# Schematic.net
KiCad netlist of a schematic drawn in Altium Designer
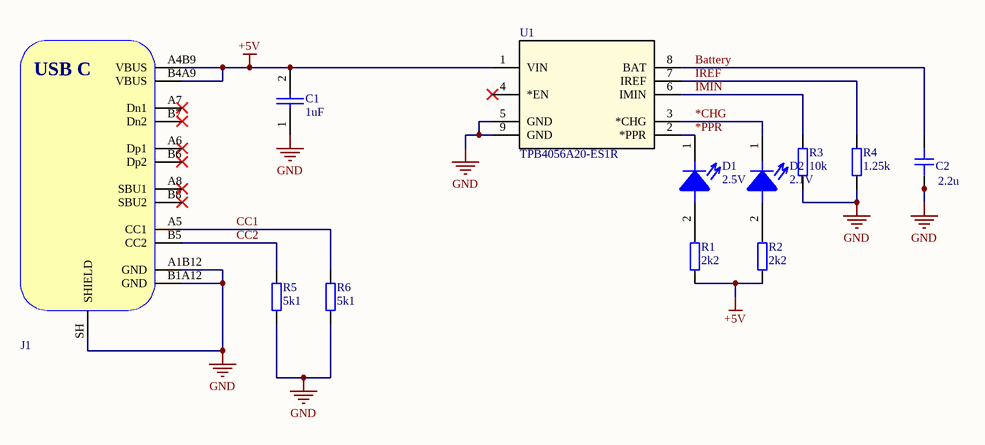
[diagram p0: Schematic.SchDoc]

(export (version "E")
  (design (tool "Eeschema 10.0.6"))
  (components
    (comp (ref "C1")
      (value "1uF")
      (footprint "CAP_0805")
      (description "CAP CER 1uF %10 0805")
      (fields
        (field (name "MANUFACTURER") "Samsung")
        (field (name "MANUFACTURER PART NUMBER") "CL21B105KBFNNNE")
        (field (name "DESIGNED BY") "Osman")
      )
      (libsource (lib "Integrated_Library1") (part "CAP CER 1uF 0805"))
    )
    (comp (ref "C2")
      (value "2.2u")
      (footprint "CAP 0805")
      (libsource (lib "Integrated_Library1") (part "CAP CER 2.2uF 16V 0805"))
    )
    (comp (ref "D1")
      (value "LS R976-NR-1")
      (footprint "LED_RED_0805")
      (description "LED Uni-Color Super Red 645nm 2-Pin Chip 0805(2012Metric) T/R")
      (fields
        (field (name "MANUFACTURER") "Osram Opto")
        (field (name "MANUFACTURER PART NUMBER") "LSR976-NR-1")
        (field (name "FORWARD VOLTAGE") "2.5V")
        (field (name "DESIGNED BY") "Osman")
      )
      (libsource (lib "Integrated_Library1") (part "LED RED 0805"))
    )
    (comp (ref "D2")
      (value "CMD17-21VGD/TR8")
      (footprint "LED_GREEN_0805")
      (description "CML CMD17-21VGD/TR8 LED SMT 0805 2.1V 7mcd 140deg Green 3K Part of the VCC Family of Products")
      (fields (field (name "MANUFACTURER") "VCC CHML") (field (name "FOWARD VOLTAGE") "2.1V"))
      (libsource (lib "Integrated_Library1") (part "LED GREEN 0805"))
    )
    (comp (ref "J1")
      (value "USB4105-GF-A-060")
      (footprint "USB4105-GF-A-060")
      (description "USB Connector, 24 Contact(s), Female, Right Angle, Solder Terminal, Locking, Receptacle")
      (fields (field (name "MANUFACTURER") "Global Connector Technology"))
      (libsource (lib "Integrated_Library1") (part "USB4105-GF-A-060"))
    )
    (comp (ref "R1")
      (value "2k2")
      (footprint "RES_0402")
      (description "Resistor SMD 0402")
      (libsource (lib "Lib1") (part "RES_0402"))
    )
    (comp (ref "R2")
      (value "2k2")
      (footprint "RES_0402")
      (description "Resistor SMD 0402")
      (libsource (lib "Lib1") (part "RES_0402"))
    )
    (comp (ref "R3")
      (value "10k")
      (footprint "RES_0402")
      (description "Resistor SMD 0402")
      (libsource (lib "Lib1") (part "RES_0402"))
    )
    (comp (ref "R4")
      (value "1.25k")
      (footprint "RES_0402")
      (description "Resistor SMD 0402")
      (libsource (lib "Lib1") (part "RES_0402"))
    )
    (comp (ref "R5")
      (value "5k1")
      (footprint "RES_0402")
      (description "Resistor SMD 0402")
      (libsource (lib "Lib1") (part "RES_0402"))
    )
    (comp (ref "R6")
      (value "5k1")
      (footprint "RES_0402")
      (description "Resistor SMD 0402")
      (libsource (lib "Lib1") (part "RES_0402"))
    )
    (comp (ref "U1")
      (value "TPB4056A20-ES1R")
      (footprint "ESOP-8_TPK - duplicate")
      (description "No Description Available")
      (libsource (lib "Integrated_Library1") (part "TPB4056A20-ES1R"))
    )
  )
  (nets
    (net (code "1") (name "+5V") (class "Default")
      (node (ref "C1") (pin "2") (pinfunction "2_2") (pintype "passive"))
      (node (ref "J1") (pin "A4B9") (pinfunction "VBUS_A4B9") (pintype "passive"))
      (node (ref "J1") (pin "B4A9") (pinfunction "VBUS_B4A9") (pintype "passive"))
      (node (ref "R1") (pin "1") (pinfunction "1_1") (pintype "passive"))
      (node (ref "R2") (pin "1") (pinfunction "1_1") (pintype "passive"))
      (node (ref "U1") (pin "1") (pinfunction "VIN_1") (pintype "passive"))
    )
    (net (code "2") (name "/*CHG") (class "Default")
      (node (ref "D2") (pin "1") (pinfunction "1_1") (pintype "passive"))
      (node (ref "U1") (pin "3") (pinfunction "*CHG_3") (pintype "passive"))
    )
    (net (code "3") (name "/*PPR") (class "Default")
      (node (ref "D1") (pin "1") (pinfunction "1_1") (pintype "passive"))
      (node (ref "U1") (pin "2") (pinfunction "*PPR_2") (pintype "passive"))
    )
    (net (code "4") (name "/Battery") (class "Default")
      (node (ref "C2") (pin "2") (pinfunction "2_2") (pintype "passive"))
      (node (ref "U1") (pin "8") (pinfunction "BAT_8") (pintype "passive"))
    )
    (net (code "5") (name "/CC1") (class "Default")
      (node (ref "J1") (pin "A5") (pinfunction "CC1_A5") (pintype "passive"))
      (node (ref "R6") (pin "2") (pinfunction "2_2") (pintype "passive"))
    )
    (net (code "6") (name "/CC2") (class "Default")
      (node (ref "J1") (pin "B5") (pinfunction "CC2_B5") (pintype "passive"))
      (node (ref "R5") (pin "2") (pinfunction "2_2") (pintype "passive"))
    )
    (net (code "7") (name "/IMIN") (class "Default")
      (node (ref "R3") (pin "2") (pinfunction "2_2") (pintype "passive"))
      (node (ref "U1") (pin "6") (pinfunction "IMIN_6") (pintype "passive"))
    )
    (net (code "8") (name "/IREF") (class "Default")
      (node (ref "R4") (pin "2") (pinfunction "2_2") (pintype "passive"))
      (node (ref "U1") (pin "7") (pinfunction "IREF_7") (pintype "passive"))
    )
    (net (code "9") (name "GND") (class "Default")
      (node (ref "C1") (pin "1") (pinfunction "1_1") (pintype "passive"))
      (node (ref "C2") (pin "1") (pinfunction "1_1") (pintype "passive"))
      (node (ref "J1") (pin "A1B12") (pinfunction "GND_A1B12") (pintype "passive"))
      (node (ref "J1") (pin "B1A12") (pinfunction "GND_B1A12") (pintype "passive"))
      (node (ref "J1") (pin "SH") (pinfunction "SHIELD_SH") (pintype "passive"))
      (node (ref "R3") (pin "1") (pinfunction "1_1") (pintype "passive"))
      (node (ref "R4") (pin "1") (pinfunction "1_1") (pintype "passive"))
      (node (ref "R5") (pin "1") (pinfunction "1_1") (pintype "passive"))
      (node (ref "R6") (pin "1") (pinfunction "1_1") (pintype "passive"))
      (node (ref "U1") (pin "5") (pinfunction "GND_5") (pintype "passive"))
      (node (ref "U1") (pin "9") (pinfunction "GND_9") (pintype "passive"))
    )
    (net (code "10") (name "Net-(D1-Pad2)") (class "Default")
      (node (ref "D1") (pin "2") (pinfunction "2_2") (pintype "passive"))
      (node (ref "R1") (pin "2") (pinfunction "2_2") (pintype "passive"))
    )
    (net (code "11") (name "Net-(D2-Pad2)") (class "Default")
      (node (ref "D2") (pin "2") (pinfunction "2_2") (pintype "passive"))
      (node (ref "R2") (pin "2") (pinfunction "2_2") (pintype "passive"))
    )
    (net (code "12") (name "unconnected-(J1-Dn1-PadA7)") (class "Default")
      (node (ref "J1") (pin "A7") (pinfunction "Dn1_A7") (pintype "passive+no_connect"))
    )
    (net (code "13") (name "unconnected-(J1-Dn2-PadB7)") (class "Default")
      (node (ref "J1") (pin "B7") (pinfunction "Dn2_B7") (pintype "passive+no_connect"))
    )
    (net (code "14") (name "unconnected-(J1-Dp1-PadA6)") (class "Default")
      (node (ref "J1") (pin "A6") (pinfunction "Dp1_A6") (pintype "passive+no_connect"))
    )
    (net (code "15") (name "unconnected-(J1-Dp2-PadB6)") (class "Default")
      (node (ref "J1") (pin "B6") (pinfunction "Dp2_B6") (pintype "passive+no_connect"))
    )
    (net (code "16") (name "unconnected-(J1-SBU1-PadA8)") (class "Default")
      (node (ref "J1") (pin "A8") (pinfunction "SBU1_A8") (pintype "passive+no_connect"))
    )
    (net (code "17") (name "unconnected-(J1-SBU2-PadB8)") (class "Default")
      (node (ref "J1") (pin "B8") (pinfunction "SBU2_B8") (pintype "passive+no_connect"))
    )
    (net (code "18") (name "unconnected-(U1-*EN-Pad4)") (class "Default")
      (node (ref "U1") (pin "4") (pinfunction "*EN_4") (pintype "passive+no_connect"))
    )
  )
)
